# Mainboard.net
KiCad netlist of a schematic drawn in EAGLE
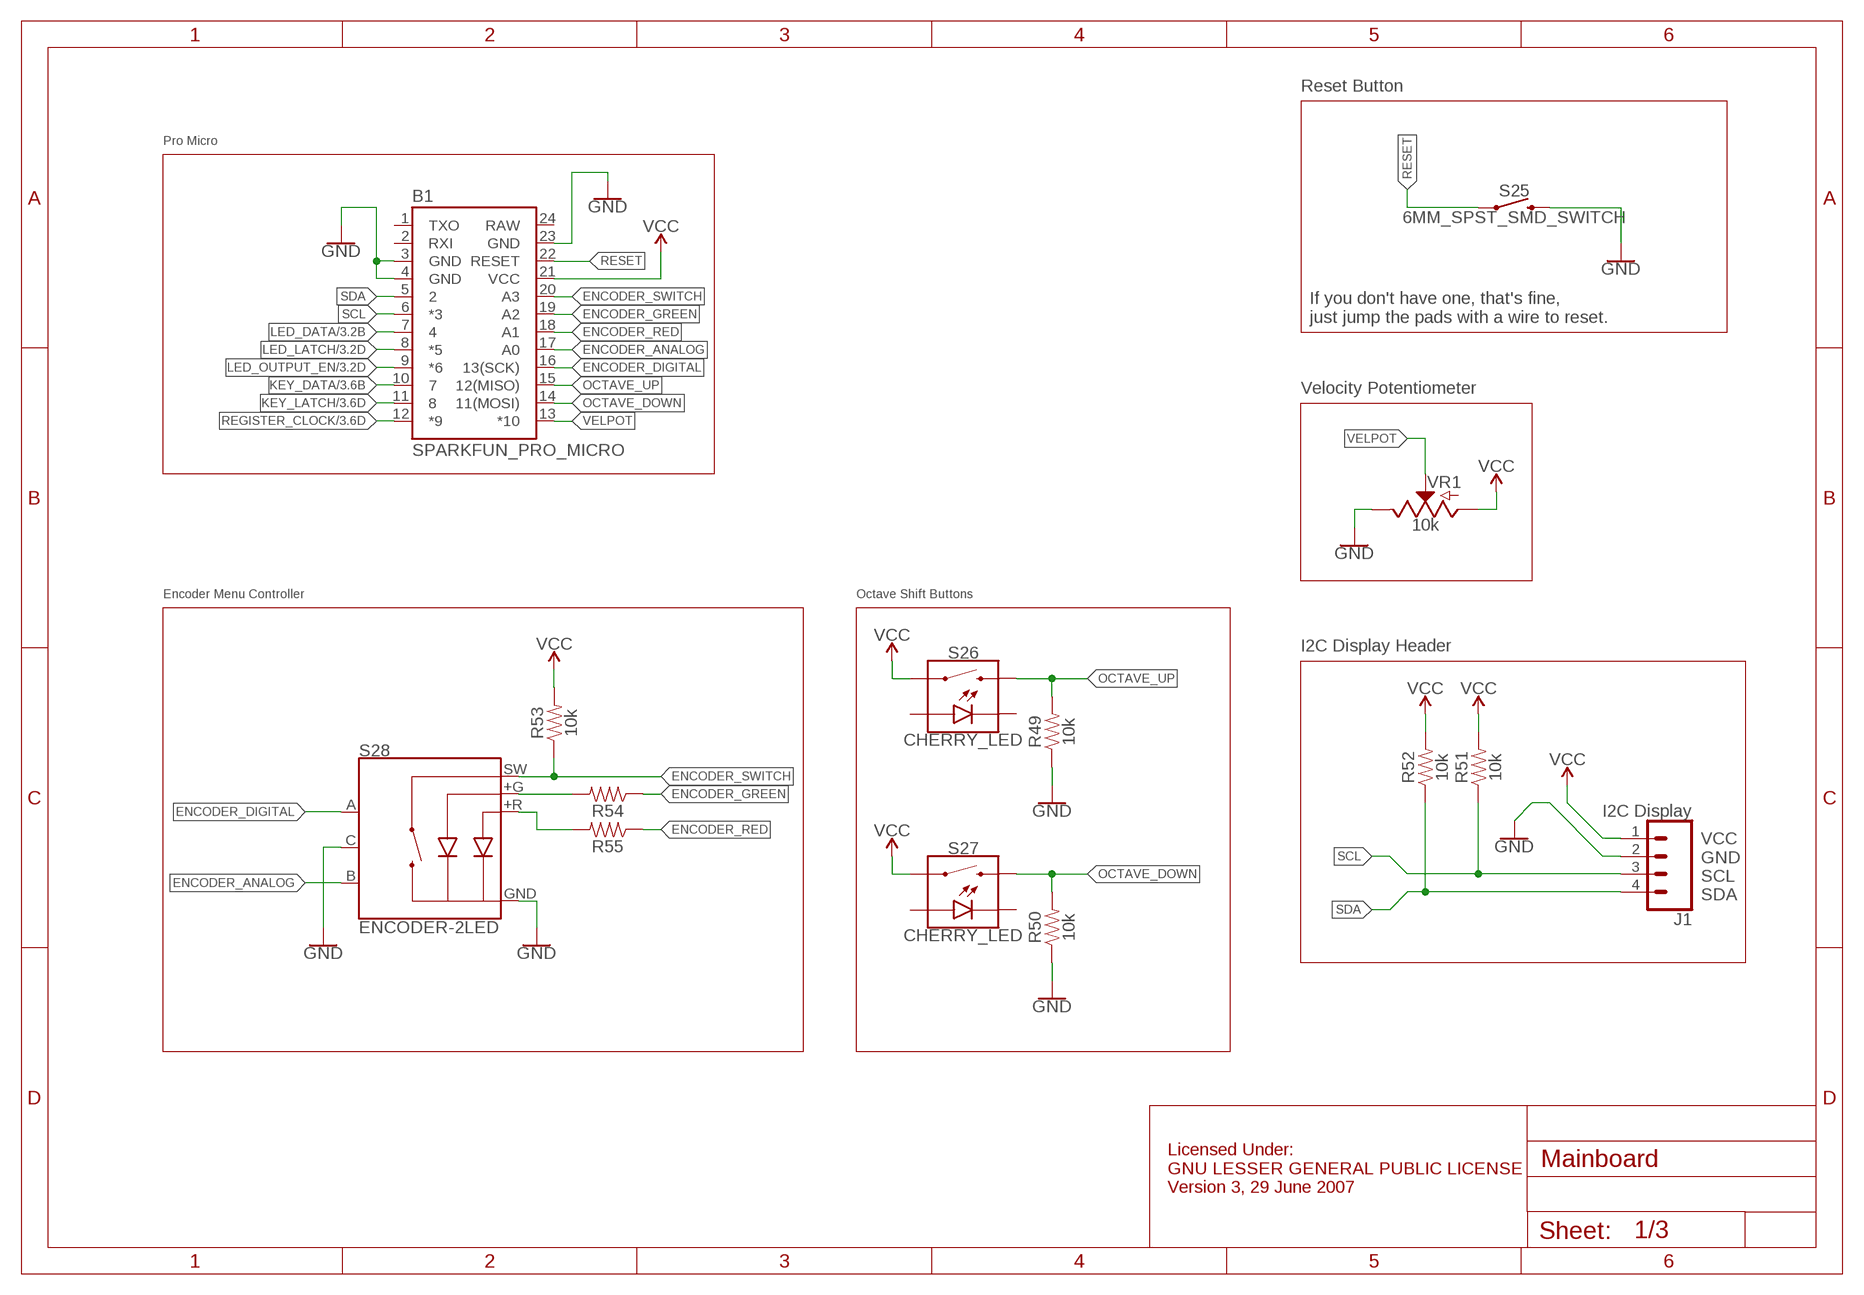
[diagram p0: schematic, sheet 1]
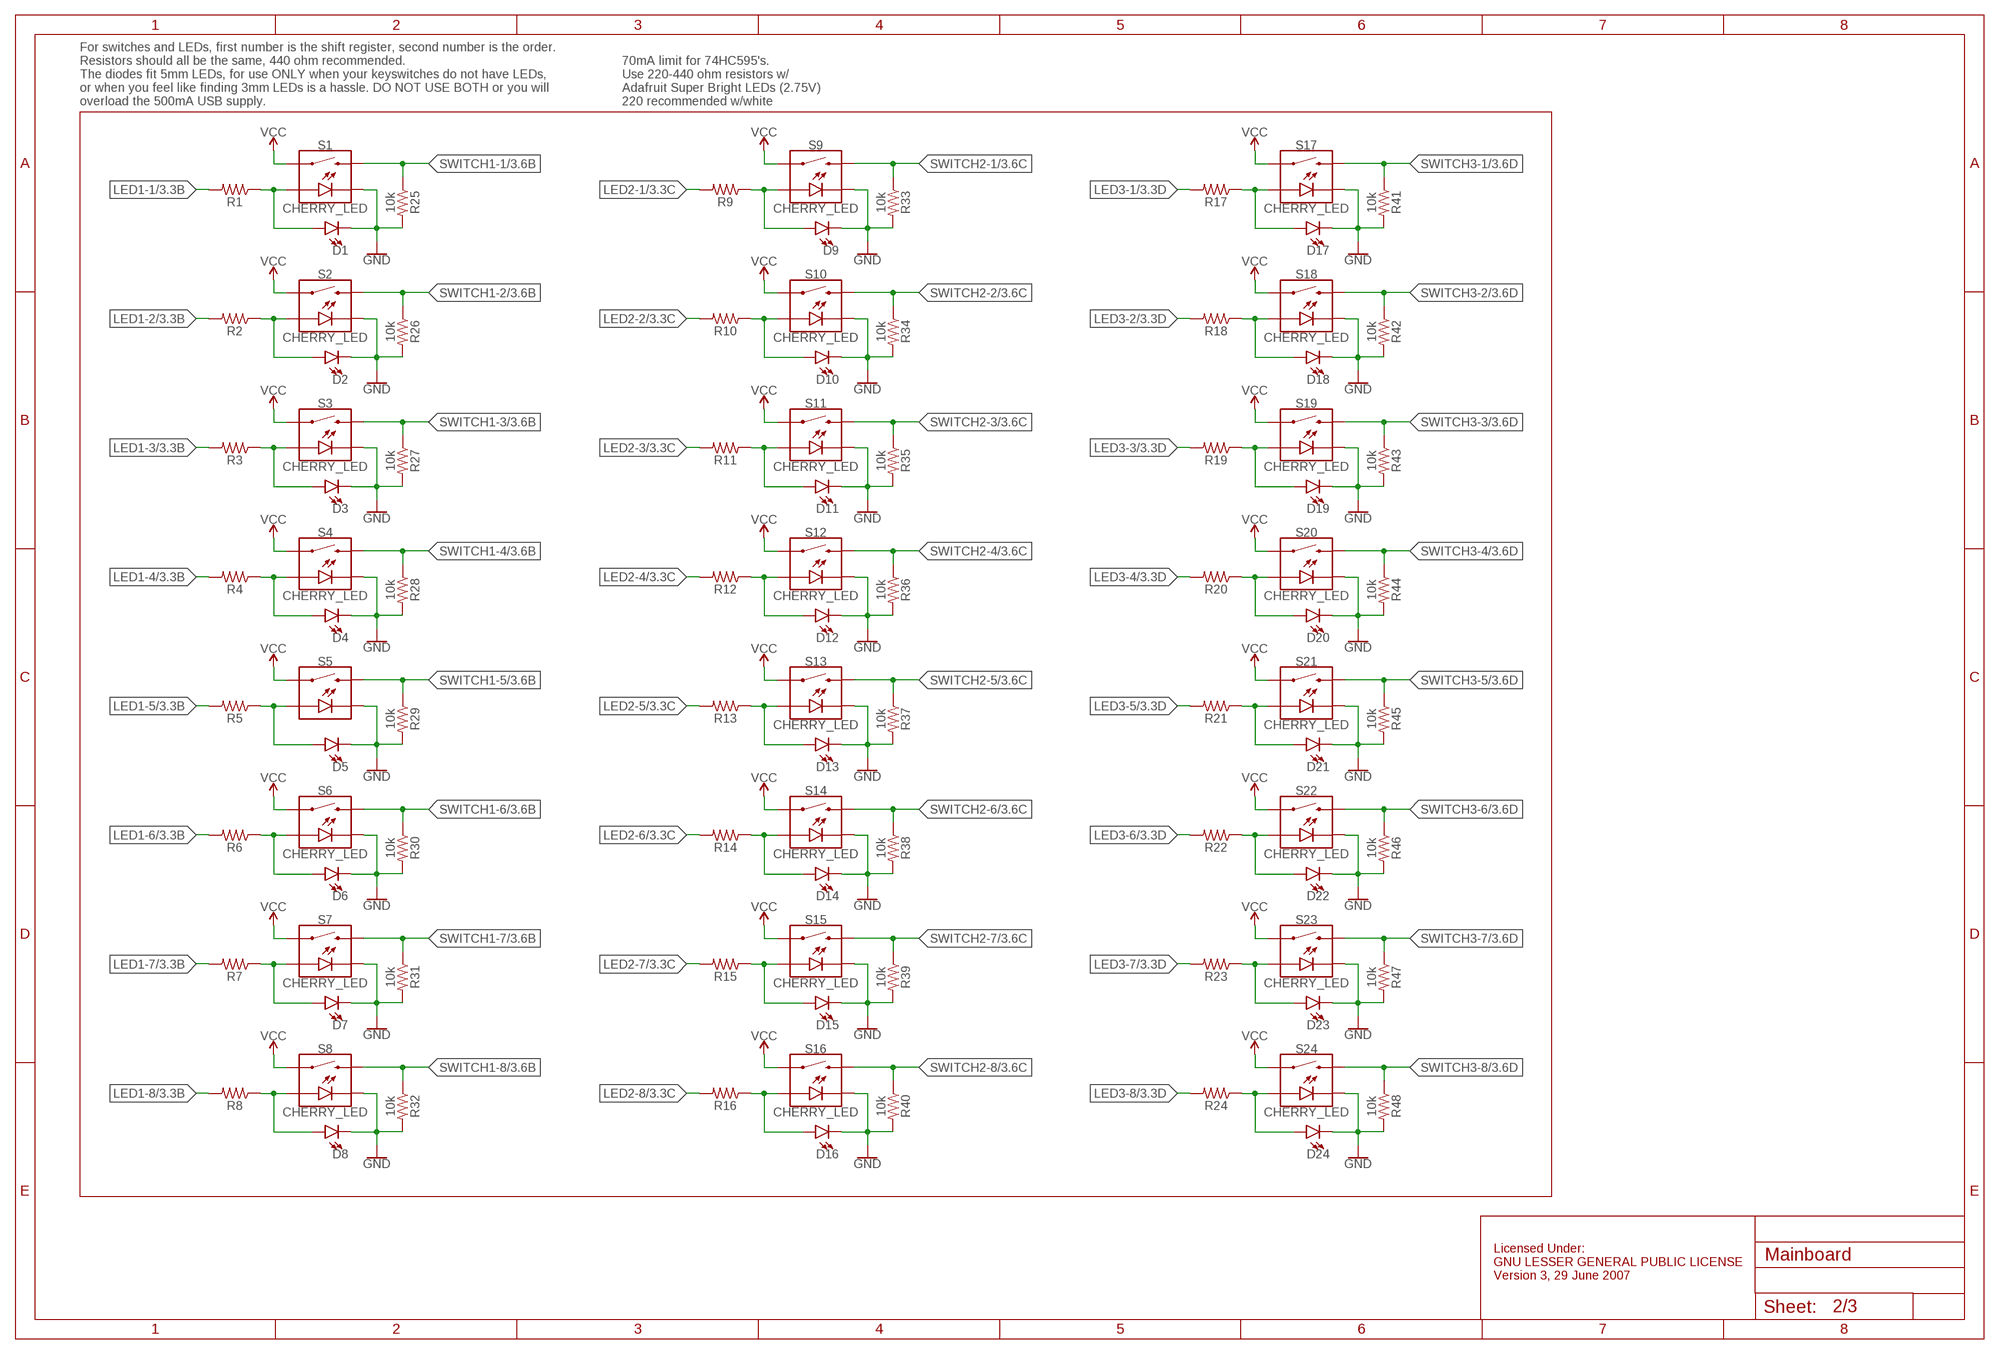
[diagram p1: schematic, sheet 2]
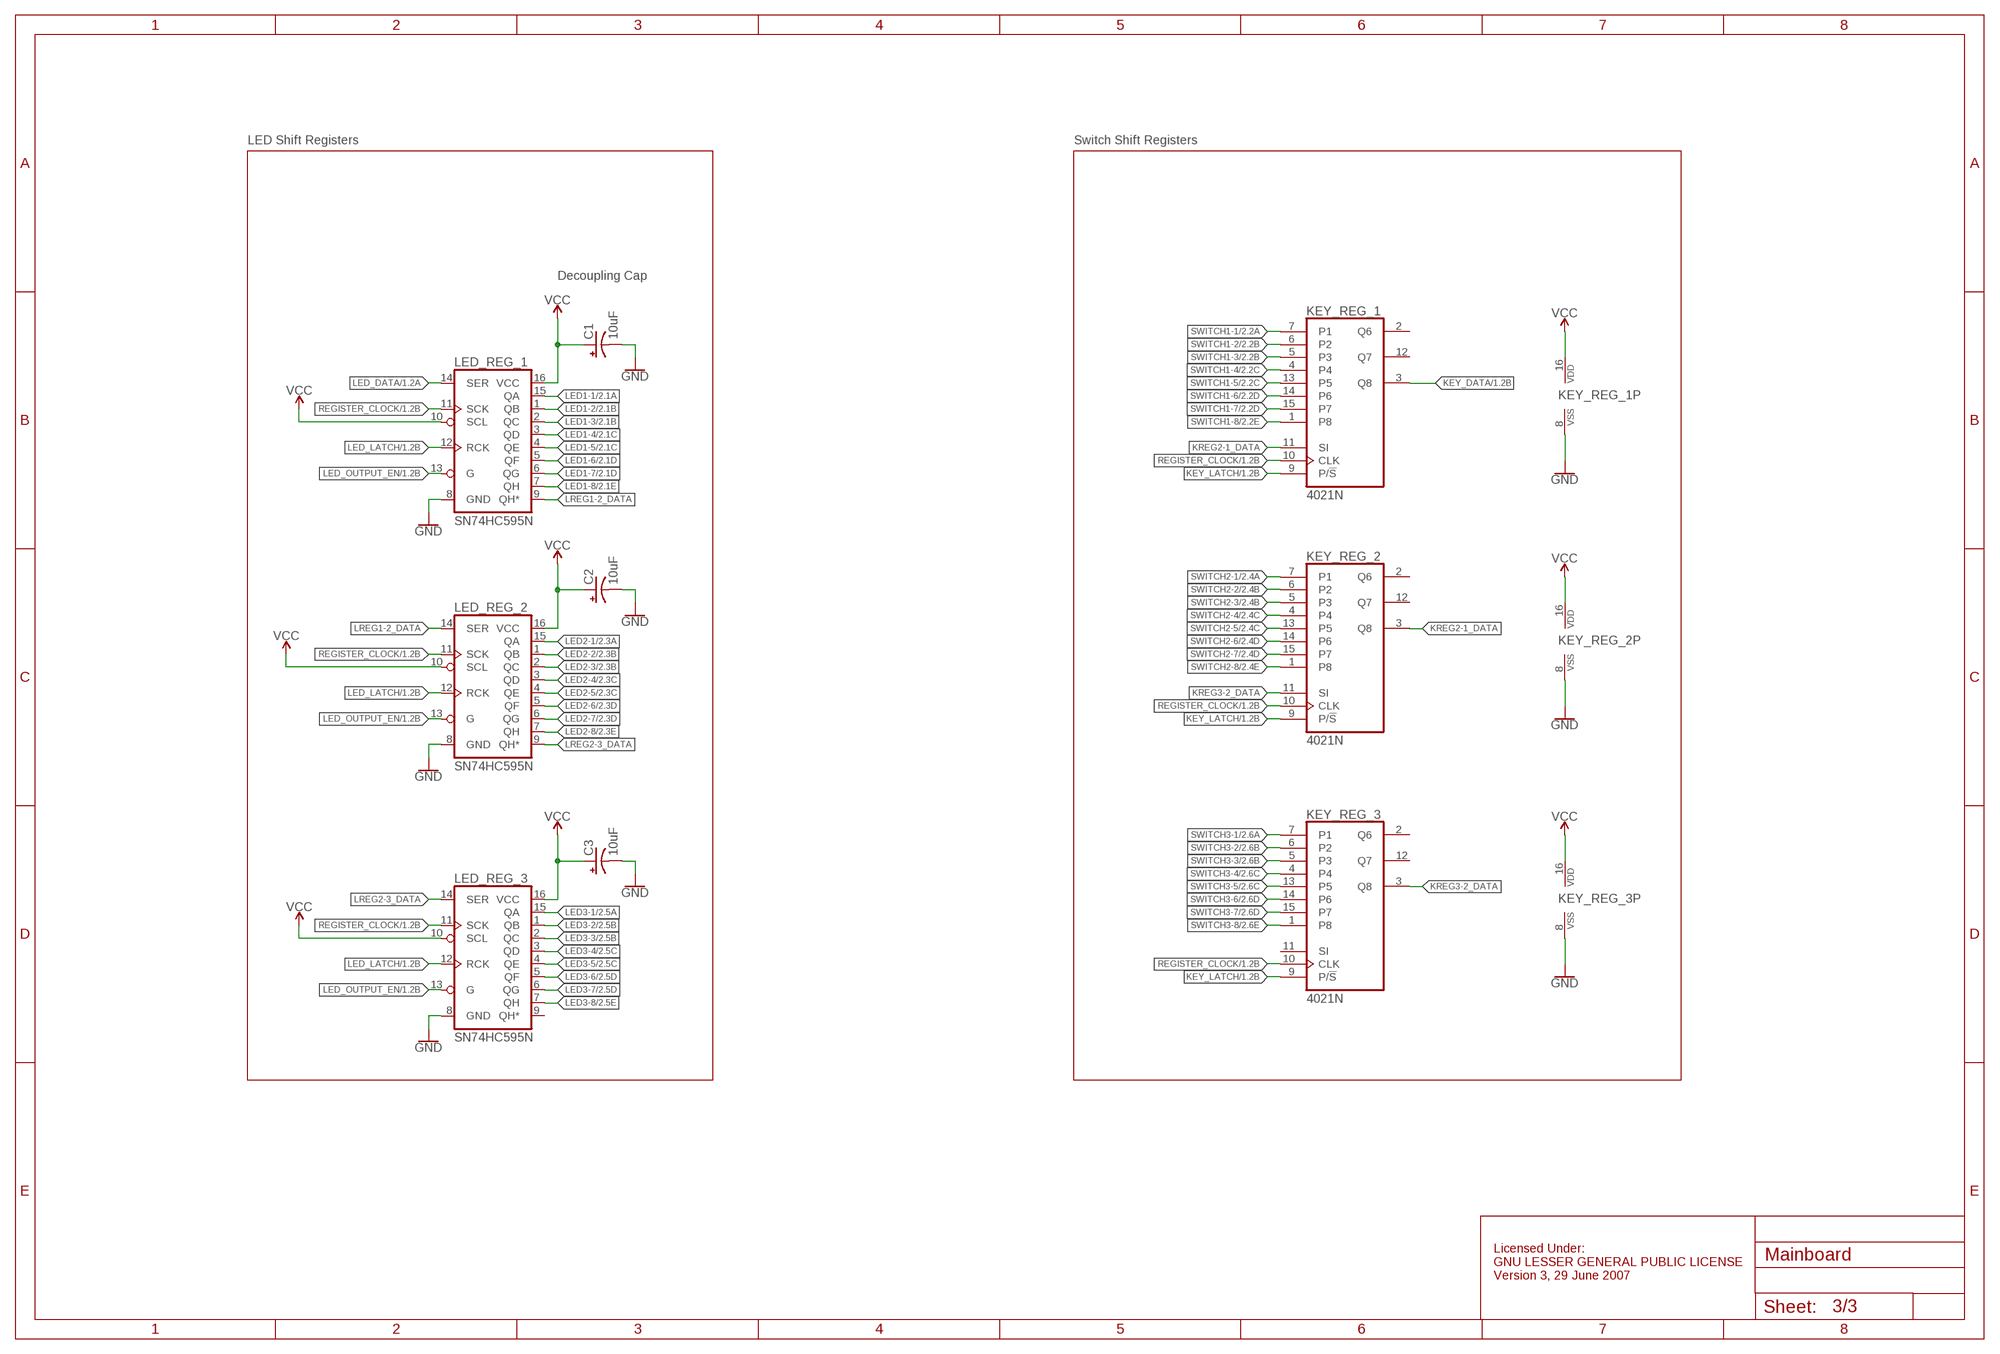
[diagram p2: schematic, sheet 3]

(export (version "E")
  (design (tool "Eeschema 10.0.6"))
  (components
    (comp (ref "D1")
      (value "LED5MM")
      (footprint "eagle-import:LED_5MM")
      (libsource (lib "eagle-import") (part "LED5MM"))
    )
    (comp (ref "D2")
      (value "LED5MM")
      (footprint "eagle-import:LED_5MM")
      (libsource (lib "eagle-import") (part "LED5MM"))
    )
    (comp (ref "D3")
      (value "LED5MM")
      (footprint "eagle-import:LED_5MM")
      (libsource (lib "eagle-import") (part "LED5MM"))
    )
    (comp (ref "D4")
      (value "LED5MM")
      (footprint "eagle-import:LED_5MM")
      (libsource (lib "eagle-import") (part "LED5MM"))
    )
    (comp (ref "D5")
      (value "LED5MM")
      (footprint "eagle-import:LED_5MM")
      (libsource (lib "eagle-import") (part "LED5MM"))
    )
    (comp (ref "D6")
      (value "LED5MM")
      (footprint "eagle-import:LED_5MM")
      (libsource (lib "eagle-import") (part "LED5MM"))
    )
    (comp (ref "D7")
      (value "LED5MM")
      (footprint "eagle-import:LED_5MM")
      (libsource (lib "eagle-import") (part "LED5MM"))
    )
    (comp (ref "D8")
      (value "LED5MM")
      (footprint "eagle-import:LED_5MM")
      (libsource (lib "eagle-import") (part "LED5MM"))
    )
    (comp (ref "D9")
      (value "LED5MM")
      (footprint "eagle-import:LED_5MM")
      (libsource (lib "eagle-import") (part "LED5MM"))
    )
    (comp (ref "D10")
      (value "LED5MM")
      (footprint "eagle-import:LED_5MM")
      (libsource (lib "eagle-import") (part "LED5MM"))
    )
    (comp (ref "D11")
      (value "LED5MM")
      (footprint "eagle-import:LED_5MM")
      (libsource (lib "eagle-import") (part "LED5MM"))
    )
    (comp (ref "D12")
      (value "LED5MM")
      (footprint "eagle-import:LED_5MM")
      (libsource (lib "eagle-import") (part "LED5MM"))
    )
    (comp (ref "D13")
      (value "LED5MM")
      (footprint "eagle-import:LED_5MM")
      (libsource (lib "eagle-import") (part "LED5MM"))
    )
    (comp (ref "D14")
      (value "LED5MM")
      (footprint "eagle-import:LED_5MM")
      (libsource (lib "eagle-import") (part "LED5MM"))
    )
    (comp (ref "D15")
      (value "LED5MM")
      (footprint "eagle-import:LED_5MM")
      (libsource (lib "eagle-import") (part "LED5MM"))
    )
    (comp (ref "D16")
      (value "LED5MM")
      (footprint "eagle-import:LED_5MM")
      (libsource (lib "eagle-import") (part "LED5MM"))
    )
    (comp (ref "D17")
      (value "LED5MM")
      (footprint "eagle-import:LED_5MM")
      (libsource (lib "eagle-import") (part "LED5MM"))
    )
    (comp (ref "D18")
      (value "LED5MM")
      (footprint "eagle-import:LED_5MM")
      (libsource (lib "eagle-import") (part "LED5MM"))
    )
    (comp (ref "D19")
      (value "LED5MM")
      (footprint "eagle-import:LED_5MM")
      (libsource (lib "eagle-import") (part "LED5MM"))
    )
    (comp (ref "D20")
      (value "LED5MM")
      (footprint "eagle-import:LED_5MM")
      (libsource (lib "eagle-import") (part "LED5MM"))
    )
    (comp (ref "D21")
      (value "LED5MM")
      (footprint "eagle-import:LED_5MM")
      (libsource (lib "eagle-import") (part "LED5MM"))
    )
    (comp (ref "D22")
      (value "LED5MM")
      (footprint "eagle-import:LED_5MM")
      (libsource (lib "eagle-import") (part "LED5MM"))
    )
    (comp (ref "D23")
      (value "LED5MM")
      (footprint "eagle-import:LED_5MM")
      (libsource (lib "eagle-import") (part "LED5MM"))
    )
    (comp (ref "D24")
      (value "LED5MM")
      (footprint "eagle-import:LED_5MM")
      (libsource (lib "eagle-import") (part "LED5MM"))
    )
    (comp (ref "R1")
      (value "RESISTORAXIAL-0.3")
      (footprint "eagle-import:AXIAL-0.3")
      (libsource (lib "eagle-import") (part "RESISTORAXIAL-0.3"))
    )
    (comp (ref "R2")
      (value "RESISTORAXIAL-0.3")
      (footprint "eagle-import:AXIAL-0.3")
      (libsource (lib "eagle-import") (part "RESISTORAXIAL-0.3"))
    )
    (comp (ref "R3")
      (value "RESISTORAXIAL-0.3")
      (footprint "eagle-import:AXIAL-0.3")
      (libsource (lib "eagle-import") (part "RESISTORAXIAL-0.3"))
    )
    (comp (ref "R4")
      (value "RESISTORAXIAL-0.3")
      (footprint "eagle-import:AXIAL-0.3")
      (libsource (lib "eagle-import") (part "RESISTORAXIAL-0.3"))
    )
    (comp (ref "R5")
      (value "RESISTORAXIAL-0.3")
      (footprint "eagle-import:AXIAL-0.3")
      (libsource (lib "eagle-import") (part "RESISTORAXIAL-0.3"))
    )
    (comp (ref "R6")
      (value "RESISTORAXIAL-0.3")
      (footprint "eagle-import:AXIAL-0.3")
      (libsource (lib "eagle-import") (part "RESISTORAXIAL-0.3"))
    )
    (comp (ref "R7")
      (value "RESISTORAXIAL-0.3")
      (footprint "eagle-import:AXIAL-0.3")
      (libsource (lib "eagle-import") (part "RESISTORAXIAL-0.3"))
    )
    (comp (ref "R8")
      (value "RESISTORAXIAL-0.3")
      (footprint "eagle-import:AXIAL-0.3")
      (libsource (lib "eagle-import") (part "RESISTORAXIAL-0.3"))
    )
    (comp (ref "R9")
      (value "RESISTORAXIAL-0.3")
      (footprint "eagle-import:AXIAL-0.3")
      (libsource (lib "eagle-import") (part "RESISTORAXIAL-0.3"))
    )
    (comp (ref "R10")
      (value "RESISTORAXIAL-0.3")
      (footprint "eagle-import:AXIAL-0.3")
      (libsource (lib "eagle-import") (part "RESISTORAXIAL-0.3"))
    )
    (comp (ref "R11")
      (value "RESISTORAXIAL-0.3")
      (footprint "eagle-import:AXIAL-0.3")
      (libsource (lib "eagle-import") (part "RESISTORAXIAL-0.3"))
    )
    (comp (ref "R12")
      (value "RESISTORAXIAL-0.3")
      (footprint "eagle-import:AXIAL-0.3")
      (libsource (lib "eagle-import") (part "RESISTORAXIAL-0.3"))
    )
    (comp (ref "R13")
      (value "RESISTORAXIAL-0.3")
      (footprint "eagle-import:AXIAL-0.3")
      (libsource (lib "eagle-import") (part "RESISTORAXIAL-0.3"))
    )
    (comp (ref "R14")
      (value "RESISTORAXIAL-0.3")
      (footprint "eagle-import:AXIAL-0.3")
      (libsource (lib "eagle-import") (part "RESISTORAXIAL-0.3"))
    )
    (comp (ref "R15")
      (value "RESISTORAXIAL-0.3")
      (footprint "eagle-import:AXIAL-0.3")
      (libsource (lib "eagle-import") (part "RESISTORAXIAL-0.3"))
    )
    (comp (ref "R16")
      (value "RESISTORAXIAL-0.3")
      (footprint "eagle-import:AXIAL-0.3")
      (libsource (lib "eagle-import") (part "RESISTORAXIAL-0.3"))
    )
    (comp (ref "R17")
      (value "RESISTORAXIAL-0.3")
      (footprint "eagle-import:AXIAL-0.3")
      (libsource (lib "eagle-import") (part "RESISTORAXIAL-0.3"))
    )
    (comp (ref "R18")
      (value "RESISTORAXIAL-0.3")
      (footprint "eagle-import:AXIAL-0.3")
      (libsource (lib "eagle-import") (part "RESISTORAXIAL-0.3"))
    )
    (comp (ref "R19")
      (value "RESISTORAXIAL-0.3")
      (footprint "eagle-import:AXIAL-0.3")
      (libsource (lib "eagle-import") (part "RESISTORAXIAL-0.3"))
    )
    (comp (ref "R20")
      (value "RESISTORAXIAL-0.3")
      (footprint "eagle-import:AXIAL-0.3")
      (libsource (lib "eagle-import") (part "RESISTORAXIAL-0.3"))
    )
    (comp (ref "R21")
      (value "RESISTORAXIAL-0.3")
      (footprint "eagle-import:AXIAL-0.3")
      (libsource (lib "eagle-import") (part "RESISTORAXIAL-0.3"))
    )
    (comp (ref "R22")
      (value "RESISTORAXIAL-0.3")
      (footprint "eagle-import:AXIAL-0.3")
      (libsource (lib "eagle-import") (part "RESISTORAXIAL-0.3"))
    )
    (comp (ref "R23")
      (value "RESISTORAXIAL-0.3")
      (footprint "eagle-import:AXIAL-0.3")
      (libsource (lib "eagle-import") (part "RESISTORAXIAL-0.3"))
    )
    (comp (ref "R24")
      (value "RESISTORAXIAL-0.3")
      (footprint "eagle-import:AXIAL-0.3")
      (libsource (lib "eagle-import") (part "RESISTORAXIAL-0.3"))
    )
    (comp (ref "R25")
      (value "10k")
      (footprint "eagle-import:AXIAL-0.3")
      (libsource (lib "eagle-import") (part "10KOHM-HORIZ-1/4W-1%"))
    )
    (comp (ref "R26")
      (value "10k")
      (footprint "eagle-import:AXIAL-0.3")
      (libsource (lib "eagle-import") (part "10KOHM-HORIZ-1/4W-1%"))
    )
    (comp (ref "R27")
      (value "10k")
      (footprint "eagle-import:AXIAL-0.3")
      (libsource (lib "eagle-import") (part "10KOHM-HORIZ-1/4W-1%"))
    )
    (comp (ref "R28")
      (value "10k")
      (footprint "eagle-import:AXIAL-0.3")
      (libsource (lib "eagle-import") (part "10KOHM-HORIZ-1/4W-1%"))
    )
    (comp (ref "R29")
      (value "10k")
      (footprint "eagle-import:AXIAL-0.3")
      (libsource (lib "eagle-import") (part "10KOHM-HORIZ-1/4W-1%"))
    )
    (comp (ref "R30")
      (value "10k")
      (footprint "eagle-import:AXIAL-0.3")
      (libsource (lib "eagle-import") (part "10KOHM-HORIZ-1/4W-1%"))
    )
    (comp (ref "R31")
      (value "10k")
      (footprint "eagle-import:AXIAL-0.3")
      (libsource (lib "eagle-import") (part "10KOHM-HORIZ-1/4W-1%"))
    )
    (comp (ref "R32")
      (value "10k")
      (footprint "eagle-import:AXIAL-0.3")
      (libsource (lib "eagle-import") (part "10KOHM-HORIZ-1/4W-1%"))
    )
    (comp (ref "R33")
      (value "10k")
      (footprint "eagle-import:AXIAL-0.3")
      (libsource (lib "eagle-import") (part "10KOHM-HORIZ-1/4W-1%"))
    )
    (comp (ref "R34")
      (value "10k")
      (footprint "eagle-import:AXIAL-0.3")
      (libsource (lib "eagle-import") (part "10KOHM-HORIZ-1/4W-1%"))
    )
    (comp (ref "R35")
      (value "10k")
      (footprint "eagle-import:AXIAL-0.3")
      (libsource (lib "eagle-import") (part "10KOHM-HORIZ-1/4W-1%"))
    )
    (comp (ref "R36")
      (value "10k")
      (footprint "eagle-import:AXIAL-0.3")
      (libsource (lib "eagle-import") (part "10KOHM-HORIZ-1/4W-1%"))
    )
    (comp (ref "R37")
      (value "10k")
      (footprint "eagle-import:AXIAL-0.3")
      (libsource (lib "eagle-import") (part "10KOHM-HORIZ-1/4W-1%"))
    )
    (comp (ref "R38")
      (value "10k")
      (footprint "eagle-import:AXIAL-0.3")
      (libsource (lib "eagle-import") (part "10KOHM-HORIZ-1/4W-1%"))
    )
    (comp (ref "R39")
      (value "10k")
      (footprint "eagle-import:AXIAL-0.3")
      (libsource (lib "eagle-import") (part "10KOHM-HORIZ-1/4W-1%"))
    )
    (comp (ref "R40")
      (value "10k")
      (footprint "eagle-import:AXIAL-0.3")
      (libsource (lib "eagle-import") (part "10KOHM-HORIZ-1/4W-1%"))
    )
    (comp (ref "R41")
      (value "10k")
      (footprint "eagle-import:AXIAL-0.3")
      (libsource (lib "eagle-import") (part "10KOHM-HORIZ-1/4W-1%"))
    )
    (comp (ref "R42")
      (value "10k")
      (footprint "eagle-import:AXIAL-0.3")
      (libsource (lib "eagle-import") (part "10KOHM-HORIZ-1/4W-1%"))
    )
    (comp (ref "R43")
      (value "10k")
      (footprint "eagle-import:AXIAL-0.3")
      (libsource (lib "eagle-import") (part "10KOHM-HORIZ-1/4W-1%"))
    )
    (comp (ref "R44")
      (value "10k")
      (footprint "eagle-import:AXIAL-0.3")
      (libsource (lib "eagle-import") (part "10KOHM-HORIZ-1/4W-1%"))
    )
    (comp (ref "R45")
      (value "10k")
      (footprint "eagle-import:AXIAL-0.3")
      (libsource (lib "eagle-import") (part "10KOHM-HORIZ-1/4W-1%"))
    )
    (comp (ref "R46")
      (value "10k")
      (footprint "eagle-import:AXIAL-0.3")
      (libsource (lib "eagle-import") (part "10KOHM-HORIZ-1/4W-1%"))
    )
    (comp (ref "R47")
      (value "10k")
      (footprint "eagle-import:AXIAL-0.3")
      (libsource (lib "eagle-import") (part "10KOHM-HORIZ-1/4W-1%"))
    )
    (comp (ref "R48")
      (value "10k")
      (footprint "eagle-import:AXIAL-0.3")
      (libsource (lib "eagle-import") (part "10KOHM-HORIZ-1/4W-1%"))
    )
    (comp (ref "S1")
      (value "CHERRY_LED")
      (footprint "eagle-import:CHERRY-MX-LED")
      (libsource (lib "eagle-import") (part "MOMENTARY-SWITCH-SPST-LED-PTH-CHERRY"))
    )
    (comp (ref "S2")
      (value "CHERRY_LED")
      (footprint "eagle-import:CHERRY-MX-LED")
      (libsource (lib "eagle-import") (part "MOMENTARY-SWITCH-SPST-LED-PTH-CHERRY"))
    )
    (comp (ref "S3")
      (value "CHERRY_LED")
      (footprint "eagle-import:CHERRY-MX-LED")
      (libsource (lib "eagle-import") (part "MOMENTARY-SWITCH-SPST-LED-PTH-CHERRY"))
    )
    (comp (ref "S4")
      (value "CHERRY_LED")
      (footprint "eagle-import:CHERRY-MX-LED")
      (libsource (lib "eagle-import") (part "MOMENTARY-SWITCH-SPST-LED-PTH-CHERRY"))
    )
    (comp (ref "S5")
      (value "MOMENTARY-SWITCH-SPST-LED-PTH-CHERRY")
      (footprint "eagle-import:CHERRY-MX-LED")
      (libsource (lib "eagle-import") (part "MOMENTARY-SWITCH-SPST-LED-PTH-CHERRY"))
    )
    (comp (ref "S6")
      (value "CHERRY_LED")
      (footprint "eagle-import:CHERRY-MX-LED")
      (libsource (lib "eagle-import") (part "MOMENTARY-SWITCH-SPST-LED-PTH-CHERRY"))
    )
    (comp (ref "S7")
      (value "CHERRY_LED")
      (footprint "eagle-import:CHERRY-MX-LED")
      (libsource (lib "eagle-import") (part "MOMENTARY-SWITCH-SPST-LED-PTH-CHERRY"))
    )
    (comp (ref "S8")
      (value "CHERRY_LED")
      (footprint "eagle-import:CHERRY-MX-LED")
      (libsource (lib "eagle-import") (part "MOMENTARY-SWITCH-SPST-LED-PTH-CHERRY"))
    )
    (comp (ref "S9")
      (value "CHERRY_LED")
      (footprint "eagle-import:CHERRY-MX-LED")
      (libsource (lib "eagle-import") (part "MOMENTARY-SWITCH-SPST-LED-PTH-CHERRY"))
    )
    (comp (ref "S10")
      (value "CHERRY_LED")
      (footprint "eagle-import:CHERRY-MX-LED")
      (libsource (lib "eagle-import") (part "MOMENTARY-SWITCH-SPST-LED-PTH-CHERRY"))
    )
    (comp (ref "S11")
      (value "CHERRY_LED")
      (footprint "eagle-import:CHERRY-MX-LED")
      (libsource (lib "eagle-import") (part "MOMENTARY-SWITCH-SPST-LED-PTH-CHERRY"))
    )
    (comp (ref "S12")
      (value "CHERRY_LED")
      (footprint "eagle-import:CHERRY-MX-LED")
      (libsource (lib "eagle-import") (part "MOMENTARY-SWITCH-SPST-LED-PTH-CHERRY"))
    )
    (comp (ref "S13")
      (value "CHERRY_LED")
      (footprint "eagle-import:CHERRY-MX-LED")
      (libsource (lib "eagle-import") (part "MOMENTARY-SWITCH-SPST-LED-PTH-CHERRY"))
    )
    (comp (ref "S14")
      (value "CHERRY_LED")
      (footprint "eagle-import:CHERRY-MX-LED")
      (libsource (lib "eagle-import") (part "MOMENTARY-SWITCH-SPST-LED-PTH-CHERRY"))
    )
    (comp (ref "S15")
      (value "CHERRY_LED")
      (footprint "eagle-import:CHERRY-MX-LED")
      (libsource (lib "eagle-import") (part "MOMENTARY-SWITCH-SPST-LED-PTH-CHERRY"))
    )
    (comp (ref "S16")
      (value "CHERRY_LED")
      (footprint "eagle-import:CHERRY-MX-LED")
      (libsource (lib "eagle-import") (part "MOMENTARY-SWITCH-SPST-LED-PTH-CHERRY"))
    )
    (comp (ref "S17")
      (value "CHERRY_LED")
      (footprint "eagle-import:CHERRY-MX-LED")
      (libsource (lib "eagle-import") (part "MOMENTARY-SWITCH-SPST-LED-PTH-CHERRY"))
    )
    (comp (ref "S18")
      (value "CHERRY_LED")
      (footprint "eagle-import:CHERRY-MX-LED")
      (libsource (lib "eagle-import") (part "MOMENTARY-SWITCH-SPST-LED-PTH-CHERRY"))
    )
    (comp (ref "S19")
      (value "CHERRY_LED")
      (footprint "eagle-import:CHERRY-MX-LED")
      (libsource (lib "eagle-import") (part "MOMENTARY-SWITCH-SPST-LED-PTH-CHERRY"))
    )
    (comp (ref "S20")
      (value "CHERRY_LED")
      (footprint "eagle-import:CHERRY-MX-LED")
      (libsource (lib "eagle-import") (part "MOMENTARY-SWITCH-SPST-LED-PTH-CHERRY"))
    )
    (comp (ref "S21")
      (value "CHERRY_LED")
      (footprint "eagle-import:CHERRY-MX-LED")
      (libsource (lib "eagle-import") (part "MOMENTARY-SWITCH-SPST-LED-PTH-CHERRY"))
    )
    (comp (ref "S22")
      (value "CHERRY_LED")
      (footprint "eagle-import:CHERRY-MX-LED")
      (libsource (lib "eagle-import") (part "MOMENTARY-SWITCH-SPST-LED-PTH-CHERRY"))
    )
    (comp (ref "S23")
      (value "CHERRY_LED")
      (footprint "eagle-import:CHERRY-MX-LED")
      (libsource (lib "eagle-import") (part "MOMENTARY-SWITCH-SPST-LED-PTH-CHERRY"))
    )
    (comp (ref "S24")
      (value "CHERRY_LED")
      (footprint "eagle-import:CHERRY-MX-LED")
      (libsource (lib "eagle-import") (part "MOMENTARY-SWITCH-SPST-LED-PTH-CHERRY"))
    )
    (comp (ref "B1")
      (value "SPARKFUN_PRO_MICRO")
      (footprint "eagle-import:SPARKFUN_PRO_MICRO")
      (libsource (lib "eagle-import") (part "SPARKFUN_PRO_MICRO"))
    )
    (comp (ref "J1")
      (value "I2C Display")
      (footprint "eagle-import:1X04")
      (libsource (lib "eagle-import") (part "CONN_04"))
    )
    (comp (ref "R49")
      (value "10k")
      (footprint "eagle-import:AXIAL-0.3")
      (libsource (lib "eagle-import") (part "10KOHM-HORIZ-1/4W-1%"))
    )
    (comp (ref "R50")
      (value "10k")
      (footprint "eagle-import:AXIAL-0.3")
      (libsource (lib "eagle-import") (part "10KOHM-HORIZ-1/4W-1%"))
    )
    (comp (ref "R51")
      (value "10k")
      (footprint "eagle-import:AXIAL-0.3")
      (libsource (lib "eagle-import") (part "10KOHM-HORIZ-1/4W-1%"))
    )
    (comp (ref "R52")
      (value "10k")
      (footprint "eagle-import:AXIAL-0.3")
      (libsource (lib "eagle-import") (part "10KOHM-HORIZ-1/4W-1%"))
    )
    (comp (ref "R53")
      (value "10k")
      (footprint "eagle-import:AXIAL-0.3")
      (libsource (lib "eagle-import") (part "10KOHM-HORIZ-1/4W-1%"))
    )
    (comp (ref "R54")
      (value "RESISTORAXIAL-0.3")
      (footprint "eagle-import:AXIAL-0.3")
      (libsource (lib "eagle-import") (part "RESISTORAXIAL-0.3"))
    )
    (comp (ref "R55")
      (value "RESISTORAXIAL-0.3")
      (footprint "eagle-import:AXIAL-0.3")
      (libsource (lib "eagle-import") (part "RESISTORAXIAL-0.3"))
    )
    (comp (ref "S25")
      (value "6MM_SPST_SMD_SWITCH")
      (footprint "eagle-import:TACTILE_SWITCH_SMD_6.0X3.5MM")
      (libsource (lib "eagle-import") (part "MOMENTARY-SWITCH-SPST-SMD-6.0X3.5MM"))
    )
    (comp (ref "S26")
      (value "CHERRY_LED")
      (footprint "eagle-import:CHERRY-MX-LED")
      (libsource (lib "eagle-import") (part "MOMENTARY-SWITCH-SPST-LED-PTH-CHERRY"))
    )
    (comp (ref "S27")
      (value "CHERRY_LED")
      (footprint "eagle-import:CHERRY-MX-LED")
      (libsource (lib "eagle-import") (part "MOMENTARY-SWITCH-SPST-LED-PTH-CHERRY"))
    )
    (comp (ref "S28")
      (value "ENCODER-2LED")
      (footprint "eagle-import:ENCODER_LED_2")
      (libsource (lib "eagle-import") (part "ENCODER-2LED"))
    )
    (comp (ref "VR1")
      (value "10k")
      (footprint "eagle-import:POT-PTH-ALPS")
      (libsource (lib "eagle-import") (part "POTENTIOMETER-PTH-9MM-1/20W-20%"))
    )
    (comp (ref "C1")
      (value "10uF")
      (footprint "eagle-import:CPOL-RADIAL-2.5MM-5MM")
      (libsource (lib "eagle-import") (part "10UF-POLAR-RADIAL-2.5MM-25V-20%"))
    )
    (comp (ref "C2")
      (value "10uF")
      (footprint "eagle-import:CPOL-RADIAL-2.5MM-5MM")
      (libsource (lib "eagle-import") (part "10UF-POLAR-RADIAL-2.5MM-25V-20%"))
    )
    (comp (ref "C3")
      (value "10uF")
      (footprint "eagle-import:CPOL-RADIAL-2.5MM-5MM")
      (libsource (lib "eagle-import") (part "10UF-POLAR-RADIAL-2.5MM-25V-20%"))
    )
    (comp (ref "KEY_REG_1")
      (value "4021N")
      (footprint "eagle-import:DIL16")
      (libsource (lib "eagle-import") (part "4021N"))
    )
    (comp (ref "KEY_REG_2")
      (value "4021N")
      (footprint "eagle-import:DIL16")
      (libsource (lib "eagle-import") (part "4021N"))
    )
    (comp (ref "KEY_REG_3")
      (value "4021N")
      (footprint "eagle-import:DIL16")
      (libsource (lib "eagle-import") (part "4021N"))
    )
    (comp (ref "LED_REG_1")
      (value "SN74HC595N")
      (footprint "eagle-import:DIP16")
      (libsource (lib "eagle-import") (part "74595NHC"))
    )
    (comp (ref "LED_REG_2")
      (value "SN74HC595N")
      (footprint "eagle-import:DIP16")
      (libsource (lib "eagle-import") (part "74595NHC"))
    )
    (comp (ref "LED_REG_3")
      (value "SN74HC595N")
      (footprint "eagle-import:DIP16")
      (libsource (lib "eagle-import") (part "74595NHC"))
    )
  )
  (nets
    (net (code "1") (name "ENCODER_ANALOG") (class "Default")
      (node (ref "B1") (pin "17") (pinfunction "A0_17") (pintype "bidirectional"))
      (node (ref "S28") (pin "B") (pinfunction "B_B") (pintype "bidirectional"))
    )
    (net (code "2") (name "ENCODER_DIGITAL") (class "Default")
      (node (ref "B1") (pin "16") (pinfunction "13(SCK)_16") (pintype "bidirectional"))
      (node (ref "S28") (pin "A") (pinfunction "A_A") (pintype "bidirectional"))
    )
    (net (code "3") (name "ENCODER_GREEN") (class "Default")
      (node (ref "B1") (pin "19") (pinfunction "A2_19") (pintype "bidirectional"))
      (node (ref "R54") (pin "P$1") (pinfunction "1_P$1") (pintype "passive"))
    )
    (net (code "4") (name "ENCODER_RED") (class "Default")
      (node (ref "B1") (pin "18") (pinfunction "A1_18") (pintype "bidirectional"))
      (node (ref "R55") (pin "P$1") (pinfunction "1_P$1") (pintype "passive"))
    )
    (net (code "5") (name "ENCODER_SWITCH") (class "Default")
      (node (ref "B1") (pin "20") (pinfunction "A3_20") (pintype "bidirectional"))
      (node (ref "R53") (pin "P$1") (pinfunction "1_P$1") (pintype "passive"))
      (node (ref "S28") (pin "SW") (pinfunction "SW_SW") (pintype "passive"))
    )
    (net (code "6") (name "GND") (class "Default")
      (node (ref "B1") (pin "23") (pinfunction "GND_23") (pintype "power_in"))
      (node (ref "B1") (pin "3") (pinfunction "GND_3") (pintype "power_in"))
      (node (ref "B1") (pin "4") (pinfunction "GND_4") (pintype "power_in"))
      (node (ref "C1") (pin "2") (pinfunction "-_2") (pintype "passive"))
      (node (ref "C2") (pin "2") (pinfunction "-_2") (pintype "passive"))
      (node (ref "C3") (pin "2") (pinfunction "-_2") (pintype "passive"))
      (node (ref "D1") (pin "K") (pinfunction "C_K") (pintype "passive"))
      (node (ref "D10") (pin "K") (pinfunction "C_K") (pintype "passive"))
      (node (ref "D11") (pin "K") (pinfunction "C_K") (pintype "passive"))
      (node (ref "D12") (pin "K") (pinfunction "C_K") (pintype "passive"))
      (node (ref "D13") (pin "K") (pinfunction "C_K") (pintype "passive"))
      (node (ref "D14") (pin "K") (pinfunction "C_K") (pintype "passive"))
      (node (ref "D15") (pin "K") (pinfunction "C_K") (pintype "passive"))
      (node (ref "D16") (pin "K") (pinfunction "C_K") (pintype "passive"))
      (node (ref "D17") (pin "K") (pinfunction "C_K") (pintype "passive"))
      (node (ref "D18") (pin "K") (pinfunction "C_K") (pintype "passive"))
      (node (ref "D19") (pin "K") (pinfunction "C_K") (pintype "passive"))
      (node (ref "D2") (pin "K") (pinfunction "C_K") (pintype "passive"))
      (node (ref "D20") (pin "K") (pinfunction "C_K") (pintype "passive"))
      (node (ref "D21") (pin "K") (pinfunction "C_K") (pintype "passive"))
      (node (ref "D22") (pin "K") (pinfunction "C_K") (pintype "passive"))
      (node (ref "D23") (pin "K") (pinfunction "C_K") (pintype "passive"))
      (node (ref "D24") (pin "K") (pinfunction "C_K") (pintype "passive"))
      (node (ref "D3") (pin "K") (pinfunction "C_K") (pintype "passive"))
      (node (ref "D4") (pin "K") (pinfunction "C_K") (pintype "passive"))
      (node (ref "D5") (pin "K") (pinfunction "C_K") (pintype "passive"))
      (node (ref "D6") (pin "K") (pinfunction "C_K") (pintype "passive"))
      (node (ref "D7") (pin "K") (pinfunction "C_K") (pintype "passive"))
      (node (ref "D8") (pin "K") (pinfunction "C_K") (pintype "passive"))
      (node (ref "D9") (pin "K") (pinfunction "C_K") (pintype "passive"))
      (node (ref "J1") (pin "2") (pinfunction "2_2") (pintype "passive"))
      (node (ref "KEY_REG_1") (pin "8") (pinfunction "VSS_8") (pintype "power_in"))
      (node (ref "KEY_REG_2") (pin "8") (pinfunction "VSS_8") (pintype "power_in"))
      (node (ref "KEY_REG_3") (pin "8") (pinfunction "VSS_8") (pintype "power_in"))
      (node (ref "LED_REG_1") (pin "8") (pinfunction "GND_8") (pintype "power_in"))
      (node (ref "LED_REG_2") (pin "8") (pinfunction "GND_8") (pintype "power_in"))
      (node (ref "LED_REG_3") (pin "8") (pinfunction "GND_8") (pintype "power_in"))
      (node (ref "R25") (pin "P$2") (pinfunction "2_P$2") (pintype "passive"))
      (node (ref "R26") (pin "P$2") (pinfunction "2_P$2") (pintype "passive"))
      (node (ref "R27") (pin "P$2") (pinfunction "2_P$2") (pintype "passive"))
      (node (ref "R28") (pin "P$2") (pinfunction "2_P$2") (pintype "passive"))
      (node (ref "R29") (pin "P$2") (pinfunction "2_P$2") (pintype "passive"))
      (node (ref "R30") (pin "P$2") (pinfunction "2_P$2") (pintype "passive"))
      (node (ref "R31") (pin "P$2") (pinfunction "2_P$2") (pintype "passive"))
      (node (ref "R32") (pin "P$2") (pinfunction "2_P$2") (pintype "passive"))
      (node (ref "R33") (pin "P$2") (pinfunction "2_P$2") (pintype "passive"))
      (node (ref "R34") (pin "P$2") (pinfunction "2_P$2") (pintype "passive"))
      (node (ref "R35") (pin "P$2") (pinfunction "2_P$2") (pintype "passive"))
      (node (ref "R36") (pin "P$2") (pinfunction "2_P$2") (pintype "passive"))
      (node (ref "R37") (pin "P$2") (pinfunction "2_P$2") (pintype "passive"))
      (node (ref "R38") (pin "P$2") (pinfunction "2_P$2") (pintype "passive"))
      (node (ref "R39") (pin "P$2") (pinfunction "2_P$2") (pintype "passive"))
      (node (ref "R40") (pin "P$2") (pinfunction "2_P$2") (pintype "passive"))
      (node (ref "R41") (pin "P$2") (pinfunction "2_P$2") (pintype "passive"))
      (node (ref "R42") (pin "P$2") (pinfunction "2_P$2") (pintype "passive"))
      (node (ref "R43") (pin "P$2") (pinfunction "2_P$2") (pintype "passive"))
      (node (ref "R44") (pin "P$2") (pinfunction "2_P$2") (pintype "passive"))
      (node (ref "R45") (pin "P$2") (pinfunction "2_P$2") (pintype "passive"))
      (node (ref "R46") (pin "P$2") (pinfunction "2_P$2") (pintype "passive"))
      (node (ref "R47") (pin "P$2") (pinfunction "2_P$2") (pintype "passive"))
      (node (ref "R48") (pin "P$2") (pinfunction "2_P$2") (pintype "passive"))
      (node (ref "R49") (pin "P$1") (pinfunction "1_P$1") (pintype "passive"))
      (node (ref "R50") (pin "P$1") (pinfunction "1_P$1") (pintype "passive"))
      (node (ref "S1") (pin "K") (pinfunction "C_K") (pintype "passive"))
      (node (ref "S10") (pin "K") (pinfunction "C_K") (pintype "passive"))
      (node (ref "S11") (pin "K") (pinfunction "C_K") (pintype "passive"))
      (node (ref "S12") (pin "K") (pinfunction "C_K") (pintype "passive"))
      (node (ref "S13") (pin "K") (pinfunction "C_K") (pintype "passive"))
      (node (ref "S14") (pin "K") (pinfunction "C_K") (pintype "passive"))
      (node (ref "S15") (pin "K") (pinfunction "C_K") (pintype "passive"))
      (node (ref "S16") (pin "K") (pinfunction "C_K") (pintype "passive"))
      (node (ref "S17") (pin "K") (pinfunction "C_K") (pintype "passive"))
      (node (ref "S18") (pin "K") (pinfunction "C_K") (pintype "passive"))
      (node (ref "S19") (pin "K") (pinfunction "C_K") (pintype "passive"))
      (node (ref "S2") (pin "K") (pinfunction "C_K") (pintype "passive"))
      (node (ref "S20") (pin "K") (pinfunction "C_K") (pintype "passive"))
      (node (ref "S21") (pin "K") (pinfunction "C_K") (pintype "passive"))
      (node (ref "S22") (pin "K") (pinfunction "C_K") (pintype "passive"))
      (node (ref "S23") (pin "K") (pinfunction "C_K") (pintype "passive"))
      (node (ref "S24") (pin "K") (pinfunction "C_K") (pintype "passive"))
      (node (ref "S25") (pin "2") (pinfunction "2_2") (pintype "passive"))
      (node (ref "S28") (pin "C") (pinfunction "C_C") (pintype "bidirectional"))
      (node (ref "S28") (pin "GND") (pinfunction "-_GND") (pintype "passive"))
      (node (ref "S3") (pin "K") (pinfunction "C_K") (pintype "passive"))
      (node (ref "S4") (pin "K") (pinfunction "C_K") (pintype "passive"))
      (node (ref "S5") (pin "K") (pinfunction "C_K") (pintype "passive"))
      (node (ref "S6") (pin "K") (pinfunction "C_K") (pintype "passive"))
      (node (ref "S7") (pin "K") (pinfunction "C_K") (pintype "passive"))
      (node (ref "S8") (pin "K") (pinfunction "C_K") (pintype "passive"))
      (node (ref "S9") (pin "K") (pinfunction "C_K") (pintype "passive"))
      (node (ref "VR1") (pin "P$1") (pinfunction "E_P$1") (pintype "passive"))
    )
    (net (code "7") (name "KEY_DATA") (class "Default")
      (node (ref "B1") (pin "10") (pinfunction "7_10") (pintype "bidirectional"))
      (node (ref "KEY_REG_1") (pin "3") (pinfunction "Q8_3") (pintype "output"))
    )
    (net (code "8") (name "KEY_LATCH") (class "Default")
      (node (ref "B1") (pin "11") (pinfunction "8_11") (pintype "bidirectional"))
      (node (ref "KEY_REG_1") (pin "9") (pinfunction "P/~{S}_9") (pintype "input"))
      (node (ref "KEY_REG_2") (pin "9") (pinfunction "P/~{S}_9") (pintype "input"))
      (node (ref "KEY_REG_3") (pin "9") (pinfunction "P/~{S}_9") (pintype "input"))
    )
    (net (code "9") (name "KREG2-1_DATA") (class "Default")
      (node (ref "KEY_REG_1") (pin "11") (pinfunction "SI_11") (pintype "input"))
      (node (ref "KEY_REG_2") (pin "3") (pinfunction "Q8_3") (pintype "output"))
    )
    (net (code "10") (name "KREG3-2_DATA") (class "Default")
      (node (ref "KEY_REG_2") (pin "11") (pinfunction "SI_11") (pintype "input"))
      (node (ref "KEY_REG_3") (pin "3") (pinfunction "Q8_3") (pintype "output"))
    )
    (net (code "11") (name "LED1-1") (class "Default")
      (node (ref "LED_REG_1") (pin "15") (pinfunction "QA_15") (pintype "tri_state"))
      (node (ref "R1") (pin "P$2") (pinfunction "2_P$2") (pintype "passive"))
    )
    (net (code "12") (name "LED1-2") (class "Default")
      (node (ref "LED_REG_1") (pin "1") (pinfunction "QB_1") (pintype "tri_state"))
      (node (ref "R2") (pin "P$2") (pinfunction "2_P$2") (pintype "passive"))
    )
    (net (code "13") (name "LED1-3") (class "Default")
      (node (ref "LED_REG_1") (pin "2") (pinfunction "QC_2") (pintype "tri_state"))
      (node (ref "R3") (pin "P$2") (pinfunction "2_P$2") (pintype "passive"))
    )
    (net (code "14") (name "LED1-4") (class "Default")
      (node (ref "LED_REG_1") (pin "3") (pinfunction "QD_3") (pintype "tri_state"))
      (node (ref "R4") (pin "P$2") (pinfunction "2_P$2") (pintype "passive"))
    )
    (net (code "15") (name "LED1-5") (class "Default")
      (node (ref "LED_REG_1") (pin "4") (pinfunction "QE_4") (pintype "tri_state"))
      (node (ref "R5") (pin "P$2") (pinfunction "2_P$2") (pintype "passive"))
    )
    (net (code "16") (name "LED1-6") (class "Default")
      (node (ref "LED_REG_1") (pin "5") (pinfunction "QF_5") (pintype "tri_state"))
      (node (ref "R6") (pin "P$2") (pinfunction "2_P$2") (pintype "passive"))
    )
    (net (code "17") (name "LED1-7") (class "Default")
      (node (ref "LED_REG_1") (pin "6") (pinfunction "QG_6") (pintype "tri_state"))
      (node (ref "R7") (pin "P$2") (pinfunction "2_P$2") (pintype "passive"))
    )
    (net (code "18") (name "LED1-8") (class "Default")
      (node (ref "LED_REG_1") (pin "7") (pinfunction "QH_7") (pintype "tri_state"))
      (node (ref "R8") (pin "P$2") (pinfunction "2_P$2") (pintype "passive"))
    )
    (net (code "19") (name "LED2-1") (class "Default")
      (node (ref "LED_REG_2") (pin "15") (pinfunction "QA_15") (pintype "tri_state"))
      (node (ref "R9") (pin "P$2") (pinfunction "2_P$2") (pintype "passive"))
    )
    (net (code "20") (name "LED2-2") (class "Default")
      (node (ref "LED_REG_2") (pin "1") (pinfunction "QB_1") (pintype "tri_state"))
      (node (ref "R10") (pin "P$2") (pinfunction "2_P$2") (pintype "passive"))
    )
    (net (code "21") (name "LED2-3") (class "Default")
      (node (ref "LED_REG_2") (pin "2") (pinfunction "QC_2") (pintype "tri_state"))
      (node (ref "R11") (pin "P$2") (pinfunction "2_P$2") (pintype "passive"))
    )
    (net (code "22") (name "LED2-4") (class "Default")
      (node (ref "LED_REG_2") (pin "3") (pinfunction "QD_3") (pintype "tri_state"))
      (node (ref "R12") (pin "P$2") (pinfunction "2_P$2") (pintype "passive"))
    )
    (net (code "23") (name "LED2-5") (class "Default")
      (node (ref "LED_REG_2") (pin "4") (pinfunction "QE_4") (pintype "tri_state"))
      (node (ref "R13") (pin "P$2") (pinfunction "2_P$2") (pintype "passive"))
    )
    (net (code "24") (name "LED2-6") (class "Default")
      (node (ref "LED_REG_2") (pin "5") (pinfunction "QF_5") (pintype "tri_state"))
      (node (ref "R14") (pin "P$2") (pinfunction "2_P$2") (pintype "passive"))
    )
    (net (code "25") (name "LED2-7") (class "Default")
      (node (ref "LED_REG_2") (pin "6") (pinfunction "QG_6") (pintype "tri_state"))
      (node (ref "R15") (pin "P$2") (pinfunction "2_P$2") (pintype "passive"))
    )
    (net (code "26") (name "LED2-8") (class "Default")
      (node (ref "LED_REG_2") (pin "7") (pinfunction "QH_7") (pintype "tri_state"))
      (node (ref "R16") (pin "P$2") (pinfunction "2_P$2") (pintype "passive"))
    )
    (net (code "27") (name "LED3-1") (class "Default")
      (node (ref "LED_REG_3") (pin "15") (pinfunction "QA_15") (pintype "tri_state"))
      (node (ref "R17") (pin "P$2") (pinfunction "2_P$2") (pintype "passive"))
    )
    (net (code "28") (name "LED3-2") (class "Default")
      (node (ref "LED_REG_3") (pin "1") (pinfunction "QB_1") (pintype "tri_state"))
      (node (ref "R18") (pin "P$2") (pinfunction "2_P$2") (pintype "passive"))
    )
    (net (code "29") (name "LED3-3") (class "Default")
      (node (ref "LED_REG_3") (pin "2") (pinfunction "QC_2") (pintype "tri_state"))
      (node (ref "R19") (pin "P$2") (pinfunction "2_P$2") (pintype "passive"))
    )
    (net (code "30") (name "LED3-4") (class "Default")
      (node (ref "LED_REG_3") (pin "3") (pinfunction "QD_3") (pintype "tri_state"))
      (node (ref "R20") (pin "P$2") (pinfunction "2_P$2") (pintype "passive"))
    )
    (net (code "31") (name "LED3-5") (class "Default")
      (node (ref "LED_REG_3") (pin "4") (pinfunction "QE_4") (pintype "tri_state"))
      (node (ref "R21") (pin "P$2") (pinfunction "2_P$2") (pintype "passive"))
    )
    (net (code "32") (name "LED3-6") (class "Default")
      (node (ref "LED_REG_3") (pin "5") (pinfunction "QF_5") (pintype "tri_state"))
      (node (ref "R22") (pin "P$2") (pinfunction "2_P$2") (pintype "passive"))
    )
    (net (code "33") (name "LED3-7") (class "Default")
      (node (ref "LED_REG_3") (pin "6") (pinfunction "QG_6") (pintype "tri_state"))
      (node (ref "R23") (pin "P$2") (pinfunction "2_P$2") (pintype "passive"))
    )
    (net (code "34") (name "LED3-8") (class "Default")
      (node (ref "LED_REG_3") (pin "7") (pinfunction "QH_7") (pintype "tri_state"))
      (node (ref "R24") (pin "P$2") (pinfunction "2_P$2") (pintype "passive"))
    )
    (net (code "35") (name "LED_DATA") (class "Default")
      (node (ref "B1") (pin "7") (pinfunction "4_7") (pintype "bidirectional"))
      (node (ref "LED_REG_1") (pin "14") (pinfunction "SER_14") (pintype "input"))
    )
    (net (code "36") (name "LED_LATCH") (class "Default")
      (node (ref "B1") (pin "8") (pinfunction "*5_8") (pintype "bidirectional"))
      (node (ref "LED_REG_1") (pin "12") (pinfunction "RCK_12") (pintype "input"))
      (node (ref "LED_REG_2") (pin "12") (pinfunction "RCK_12") (pintype "input"))
      (node (ref "LED_REG_3") (pin "12") (pinfunction "RCK_12") (pintype "input"))
    )
    (net (code "37") (name "LED_OUTPUT_EN") (class "Default")
      (node (ref "B1") (pin "9") (pinfunction "*6_9") (pintype "bidirectional"))
      (node (ref "LED_REG_1") (pin "13") (pinfunction "G_13") (pintype "input"))
      (node (ref "LED_REG_2") (pin "13") (pinfunction "G_13") (pintype "input"))
      (node (ref "LED_REG_3") (pin "13") (pinfunction "G_13") (pintype "input"))
    )
    (net (code "38") (name "LREG1-2_DATA") (class "Default")
      (node (ref "LED_REG_1") (pin "9") (pinfunction "QH*_9") (pintype "tri_state"))
      (node (ref "LED_REG_2") (pin "14") (pinfunction "SER_14") (pintype "input"))
    )
    (net (code "39") (name "LREG2-3_DATA") (class "Default")
      (node (ref "LED_REG_2") (pin "9") (pinfunction "QH*_9") (pintype "tri_state"))
      (node (ref "LED_REG_3") (pin "14") (pinfunction "SER_14") (pintype "input"))
    )
    (net (code "40") (name "Net-(R1-1)") (class "Default")
      (node (ref "D1") (pin "A") (pinfunction "A_A") (pintype "passive"))
      (node (ref "R1") (pin "P$1") (pinfunction "1_P$1") (pintype "passive"))
      (node (ref "S1") (pin "A") (pinfunction "A_A") (pintype "passive"))
    )
    (net (code "41") (name "Net-(R2-1)") (class "Default")
      (node (ref "D2") (pin "A") (pinfunction "A_A") (pintype "passive"))
      (node (ref "R2") (pin "P$1") (pinfunction "1_P$1") (pintype "passive"))
      (node (ref "S2") (pin "A") (pinfunction "A_A") (pintype "passive"))
    )
    (net (code "42") (name "Net-(R3-1)") (class "Default")
      (node (ref "D3") (pin "A") (pinfunction "A_A") (pintype "passive"))
      (node (ref "R3") (pin "P$1") (pinfunction "1_P$1") (pintype "passive"))
      (node (ref "S3") (pin "A") (pinfunction "A_A") (pintype "passive"))
    )
    (net (code "43") (name "Net-(R4-1)") (class "Default")
      (node (ref "D4") (pin "A") (pinfunction "A_A") (pintype "passive"))
      (node (ref "R4") (pin "P$1") (pinfunction "1_P$1") (pintype "passive"))
      (node (ref "S4") (pin "A") (pinfunction "A_A") (pintype "passive"))
    )
    (net (code "44") (name "Net-(R5-1)") (class "Default")
      (node (ref "D5") (pin "A") (pinfunction "A_A") (pintype "passive"))
      (node (ref "R5") (pin "P$1") (pinfunction "1_P$1") (pintype "passive"))
      (node (ref "S5") (pin "A") (pinfunction "A_A") (pintype "passive"))
    )
    (net (code "45") (name "Net-(R6-1)") (class "Default")
      (node (ref "D6") (pin "A") (pinfunction "A_A") (pintype "passive"))
      (node (ref "R6") (pin "P$1") (pinfunction "1_P$1") (pintype "passive"))
      (node (ref "S6") (pin "A") (pinfunction "A_A") (pintype "passive"))
    )
    (net (code "46") (name "Net-(R7-1)") (class "Default")
      (node (ref "D7") (pin "A") (pinfunction "A_A") (pintype "passive"))
      (node (ref "R7") (pin "P$1") (pinfunction "1_P$1") (pintype "passive"))
      (node (ref "S7") (pin "A") (pinfunction "A_A") (pintype "passive"))
    )
    (net (code "47") (name "Net-(R8-1)") (class "Default")
      (node (ref "D8") (pin "A") (pinfunction "A_A") (pintype "passive"))
      (node (ref "R8") (pin "P$1") (pinfunction "1_P$1") (pintype "passive"))
      (node (ref "S8") (pin "A") (pinfunction "A_A") (pintype "passive"))
    )
    (net (code "48") (name "Net-(R9-1)") (class "Default")
      (node (ref "D9") (pin "A") (pinfunction "A_A") (pintype "passive"))
      (node (ref "R9") (pin "P$1") (pinfunction "1_P$1") (pintype "passive"))
      (node (ref "S9") (pin "A") (pinfunction "A_A") (pintype "passive"))
    )
    (net (code "49") (name "Net-(R10-1)") (class "Default")
      (node (ref "D10") (pin "A") (pinfunction "A_A") (pintype "passive"))
      (node (ref "R10") (pin "P$1") (pinfunction "1_P$1") (pintype "passive"))
      (node (ref "S10") (pin "A") (pinfunction "A_A") (pintype "passive"))
    )
    (net (code "50") (name "Net-(R11-1)") (class "Default")
      (node (ref "D11") (pin "A") (pinfunction "A_A") (pintype "passive"))
      (node (ref "R11") (pin "P$1") (pinfunction "1_P$1") (pintype "passive"))
      (node (ref "S11") (pin "A") (pinfunction "A_A") (pintype "passive"))
    )
    (net (code "51") (name "Net-(R12-1)") (class "Default")
      (node (ref "D12") (pin "A") (pinfunction "A_A") (pintype "passive"))
      (node (ref "R12") (pin "P$1") (pinfunction "1_P$1") (pintype "passive"))
      (node (ref "S12") (pin "A") (pinfunction "A_A") (pintype "passive"))
    )
    (net (code "52") (name "Net-(R13-1)") (class "Default")
      (node (ref "D13") (pin "A") (pinfunction "A_A") (pintype "passive"))
      (node (ref "R13") (pin "P$1") (pinfunction "1_P$1") (pintype "passive"))
      (node (ref "S13") (pin "A") (pinfunction "A_A") (pintype "passive"))
    )
    (net (code "53") (name "Net-(R14-1)") (class "Default")
      (node (ref "D14") (pin "A") (pinfunction "A_A") (pintype "passive"))
      (node (ref "R14") (pin "P$1") (pinfunction "1_P$1") (pintype "passive"))
      (node (ref "S14") (pin "A") (pinfunction "A_A") (pintype "passive"))
    )
    (net (code "54") (name "Net-(R15-1)") (class "Default")
      (node (ref "D15") (pin "A") (pinfunction "A_A") (pintype "passive"))
      (node (ref "R15") (pin "P$1") (pinfunction "1_P$1") (pintype "passive"))
      (node (ref "S15") (pin "A") (pinfunction "A_A") (pintype "passive"))
    )
    (net (code "55") (name "Net-(R16-1)") (class "Default")
      (node (ref "D16") (pin "A") (pinfunction "A_A") (pintype "passive"))
      (node (ref "R16") (pin "P$1") (pinfunction "1_P$1") (pintype "passive"))
      (node (ref "S16") (pin "A") (pinfunction "A_A") (pintype "passive"))
    )
    (net (code "56") (name "Net-(R17-1)") (class "Default")
      (node (ref "D17") (pin "A") (pinfunction "A_A") (pintype "passive"))
      (node (ref "R17") (pin "P$1") (pinfunction "1_P$1") (pintype "passive"))
      (node (ref "S17") (pin "A") (pinfunction "A_A") (pintype "passive"))
    )
    (net (code "57") (name "Net-(R18-1)") (class "Default")
      (node (ref "D18") (pin "A") (pinfunction "A_A") (pintype "passive"))
      (node (ref "R18") (pin "P$1") (pinfunction "1_P$1") (pintype "passive"))
      (node (ref "S18") (pin "A") (pinfunction "A_A") (pintype "passive"))
    )
    (net (code "58") (name "Net-(R19-1)") (class "Default")
      (node (ref "D19") (pin "A") (pinfunction "A_A") (pintype "passive"))
      (node (ref "R19") (pin "P$1") (pinfunction "1_P$1") (pintype "passive"))
      (node (ref "S19") (pin "A") (pinfunction "A_A") (pintype "passive"))
    )
    (net (code "59") (name "Net-(R20-1)") (class "Default")
      (node (ref "D20") (pin "A") (pinfunction "A_A") (pintype "passive"))
      (node (ref "R20") (pin "P$1") (pinfunction "1_P$1") (pintype "passive"))
      (node (ref "S20") (pin "A") (pinfunction "A_A") (pintype "passive"))
    )
    (net (code "60") (name "Net-(R21-1)") (class "Default")
      (node (ref "D21") (pin "A") (pinfunction "A_A") (pintype "passive"))
      (node (ref "R21") (pin "P$1") (pinfunction "1_P$1") (pintype "passive"))
      (node (ref "S21") (pin "A") (pinfunction "A_A") (pintype "passive"))
    )
    (net (code "61") (name "Net-(R22-1)") (class "Default")
      (node (ref "D22") (pin "A") (pinfunction "A_A") (pintype "passive"))
      (node (ref "R22") (pin "P$1") (pinfunction "1_P$1") (pintype "passive"))
      (node (ref "S22") (pin "A") (pinfunction "A_A") (pintype "passive"))
    )
    (net (code "62") (name "Net-(R23-1)") (class "Default")
      (node (ref "D23") (pin "A") (pinfunction "A_A") (pintype "passive"))
      (node (ref "R23") (pin "P$1") (pinfunction "1_P$1") (pintype "passive"))
      (node (ref "S23") (pin "A") (pinfunction "A_A") (pintype "passive"))
    )
    (net (code "63") (name "Net-(R24-1)") (class "Default")
      (node (ref "D24") (pin "A") (pinfunction "A_A") (pintype "passive"))
      (node (ref "R24") (pin "P$1") (pinfunction "1_P$1") (pintype "passive"))
      (node (ref "S24") (pin "A") (pinfunction "A_A") (pintype "passive"))
    )
    (net (code "64") (name "Net-(R54-2)") (class "Default")
      (node (ref "R54") (pin "P$2") (pinfunction "2_P$2") (pintype "passive"))
      (node (ref "S28") (pin "+G") (pinfunction "+G_+G") (pintype "passive"))
    )
    (net (code "65") (name "Net-(R55-2)") (class "Default")
      (node (ref "R55") (pin "P$2") (pinfunction "2_P$2") (pintype "passive"))
      (node (ref "S28") (pin "+R") (pinfunction "+R_+R") (pintype "passive"))
    )
    (net (code "66") (name "OCTAVE_DOWN") (class "Default")
      (node (ref "B1") (pin "14") (pinfunction "11(MOSI)_14") (pintype "bidirectional"))
      (node (ref "R50") (pin "P$2") (pinfunction "2_P$2") (pintype "passive"))
      (node (ref "S27") (pin "S2") (pinfunction "2_S2") (pintype "passive"))
    )
    (net (code "67") (name "OCTAVE_UP") (class "Default")
      (node (ref "B1") (pin "15") (pinfunction "12(MISO)_15") (pintype "bidirectional"))
      (node (ref "R49") (pin "P$2") (pinfunction "2_P$2") (pintype "passive"))
      (node (ref "S26") (pin "S2") (pinfunction "2_S2") (pintype "passive"))
    )
    (net (code "68") (name "RAW") (class "Default")
      (node (ref "B1") (pin "24") (pinfunction "RAW_24") (pintype "power_in"))
    )
    (net (code "69") (name "REGISTER_CLOCK") (class "Default")
      (node (ref "B1") (pin "12") (pinfunction "*9_12") (pintype "bidirectional"))
      (node (ref "KEY_REG_1") (pin "10") (pinfunction "CLK_10") (pintype "input"))
      (node (ref "KEY_REG_2") (pin "10") (pinfunction "CLK_10") (pintype "input"))
      (node (ref "KEY_REG_3") (pin "10") (pinfunction "CLK_10") (pintype "input"))
      (node (ref "LED_REG_1") (pin "11") (pinfunction "SCK_11") (pintype "input"))
      (node (ref "LED_REG_2") (pin "11") (pinfunction "SCK_11") (pintype "input"))
      (node (ref "LED_REG_3") (pin "11") (pinfunction "SCK_11") (pintype "input"))
    )
    (net (code "70") (name "RESET") (class "Default")
      (node (ref "B1") (pin "22") (pinfunction "RESET_22") (pintype "bidirectional"))
      (node (ref "S25") (pin "1") (pinfunction "1_1") (pintype "passive"))
    )
    (net (code "71") (name "SCL") (class "Default")
      (node (ref "B1") (pin "6") (pinfunction "*3_6") (pintype "bidirectional"))
      (node (ref "J1") (pin "3") (pinfunction "3_3") (pintype "passive"))
      (node (ref "R51") (pin "P$1") (pinfunction "1_P$1") (pintype "passive"))
    )
    (net (code "72") (name "SDA") (class "Default")
      (node (ref "B1") (pin "5") (pinfunction "2_5") (pintype "bidirectional"))
      (node (ref "J1") (pin "4") (pinfunction "4_4") (pintype "passive"))
      (node (ref "R52") (pin "P$1") (pinfunction "1_P$1") (pintype "passive"))
    )
    (net (code "73") (name "SWITCH1-1") (class "Default")
      (node (ref "KEY_REG_1") (pin "7") (pinfunction "P1_7") (pintype "input"))
      (node (ref "R25") (pin "P$1") (pinfunction "1_P$1") (pintype "passive"))
      (node (ref "S1") (pin "S2") (pinfunction "2_S2") (pintype "passive"))
    )
    (net (code "74") (name "SWITCH1-2") (class "Default")
      (node (ref "KEY_REG_1") (pin "6") (pinfunction "P2_6") (pintype "input"))
      (node (ref "R26") (pin "P$1") (pinfunction "1_P$1") (pintype "passive"))
      (node (ref "S2") (pin "S2") (pinfunction "2_S2") (pintype "passive"))
    )
    (net (code "75") (name "SWITCH1-3") (class "Default")
      (node (ref "KEY_REG_1") (pin "5") (pinfunction "P3_5") (pintype "input"))
      (node (ref "R27") (pin "P$1") (pinfunction "1_P$1") (pintype "passive"))
      (node (ref "S3") (pin "S2") (pinfunction "2_S2") (pintype "passive"))
    )
    (net (code "76") (name "SWITCH1-4") (class "Default")
      (node (ref "KEY_REG_1") (pin "4") (pinfunction "P4_4") (pintype "input"))
      (node (ref "R28") (pin "P$1") (pinfunction "1_P$1") (pintype "passive"))
      (node (ref "S4") (pin "S2") (pinfunction "2_S2") (pintype "passive"))
    )
    (net (code "77") (name "SWITCH1-5") (class "Default")
      (node (ref "KEY_REG_1") (pin "13") (pinfunction "P5_13") (pintype "input"))
      (node (ref "R29") (pin "P$1") (pinfunction "1_P$1") (pintype "passive"))
      (node (ref "S5") (pin "S2") (pinfunction "2_S2") (pintype "passive"))
    )
    (net (code "78") (name "SWITCH1-6") (class "Default")
      (node (ref "KEY_REG_1") (pin "14") (pinfunction "P6_14") (pintype "input"))
      (node (ref "R30") (pin "P$1") (pinfunction "1_P$1") (pintype "passive"))
      (node (ref "S6") (pin "S2") (pinfunction "2_S2") (pintype "passive"))
    )
    (net (code "79") (name "SWITCH1-7") (class "Default")
      (node (ref "KEY_REG_1") (pin "15") (pinfunction "P7_15") (pintype "input"))
      (node (ref "R31") (pin "P$1") (pinfunction "1_P$1") (pintype "passive"))
      (node (ref "S7") (pin "S2") (pinfunction "2_S2") (pintype "passive"))
    )
    (net (code "80") (name "SWITCH1-8") (class "Default")
      (node (ref "KEY_REG_1") (pin "1") (pinfunction "P8_1") (pintype "input"))
      (node (ref "R32") (pin "P$1") (pinfunction "1_P$1") (pintype "passive"))
      (node (ref "S8") (pin "S2") (pinfunction "2_S2") (pintype "passive"))
    )
    (net (code "81") (name "SWITCH2-1") (class "Default")
      (node (ref "KEY_REG_2") (pin "7") (pinfunction "P1_7") (pintype "input"))
      (node (ref "R33") (pin "P$1") (pinfunction "1_P$1") (pintype "passive"))
      (node (ref "S9") (pin "S2") (pinfunction "2_S2") (pintype "passive"))
    )
    (net (code "82") (name "SWITCH2-2") (class "Default")
      (node (ref "KEY_REG_2") (pin "6") (pinfunction "P2_6") (pintype "input"))
      (node (ref "R34") (pin "P$1") (pinfunction "1_P$1") (pintype "passive"))
      (node (ref "S10") (pin "S2") (pinfunction "2_S2") (pintype "passive"))
    )
    (net (code "83") (name "SWITCH2-3") (class "Default")
      (node (ref "KEY_REG_2") (pin "5") (pinfunction "P3_5") (pintype "input"))
      (node (ref "R35") (pin "P$1") (pinfunction "1_P$1") (pintype "passive"))
      (node (ref "S11") (pin "S2") (pinfunction "2_S2") (pintype "passive"))
    )
    (net (code "84") (name "SWITCH2-4") (class "Default")
      (node (ref "KEY_REG_2") (pin "4") (pinfunction "P4_4") (pintype "input"))
      (node (ref "R36") (pin "P$1") (pinfunction "1_P$1") (pintype "passive"))
      (node (ref "S12") (pin "S2") (pinfunction "2_S2") (pintype "passive"))
    )
    (net (code "85") (name "SWITCH2-5") (class "Default")
      (node (ref "KEY_REG_2") (pin "13") (pinfunction "P5_13") (pintype "input"))
      (node (ref "R37") (pin "P$1") (pinfunction "1_P$1") (pintype "passive"))
      (node (ref "S13") (pin "S2") (pinfunction "2_S2") (pintype "passive"))
    )
    (net (code "86") (name "SWITCH2-6") (class "Default")
      (node (ref "KEY_REG_2") (pin "14") (pinfunction "P6_14") (pintype "input"))
      (node (ref "R38") (pin "P$1") (pinfunction "1_P$1") (pintype "passive"))
      (node (ref "S14") (pin "S2") (pinfunction "2_S2") (pintype "passive"))
    )
    (net (code "87") (name "SWITCH2-7") (class "Default")
      (node (ref "KEY_REG_2") (pin "15") (pinfunction "P7_15") (pintype "input"))
      (node (ref "R39") (pin "P$1") (pinfunction "1_P$1") (pintype "passive"))
      (node (ref "S15") (pin "S2") (pinfunction "2_S2") (pintype "passive"))
    )
    (net (code "88") (name "SWITCH2-8") (class "Default")
      (node (ref "KEY_REG_2") (pin "1") (pinfunction "P8_1") (pintype "input"))
      (node (ref "R40") (pin "P$1") (pinfunction "1_P$1") (pintype "passive"))
      (node (ref "S16") (pin "S2") (pinfunction "2_S2") (pintype "passive"))
    )
    (net (code "89") (name "SWITCH3-1") (class "Default")
      (node (ref "KEY_REG_3") (pin "7") (pinfunction "P1_7") (pintype "input"))
      (node (ref "R41") (pin "P$1") (pinfunction "1_P$1") (pintype "passive"))
      (node (ref "S17") (pin "S2") (pinfunction "2_S2") (pintype "passive"))
    )
    (net (code "90") (name "SWITCH3-2") (class "Default")
      (node (ref "KEY_REG_3") (pin "6") (pinfunction "P2_6") (pintype "input"))
      (node (ref "R42") (pin "P$1") (pinfunction "1_P$1") (pintype "passive"))
      (node (ref "S18") (pin "S2") (pinfunction "2_S2") (pintype "passive"))
    )
    (net (code "91") (name "SWITCH3-3") (class "Default")
      (node (ref "KEY_REG_3") (pin "5") (pinfunction "P3_5") (pintype "input"))
      (node (ref "R43") (pin "P$1") (pinfunction "1_P$1") (pintype "passive"))
      (node (ref "S19") (pin "S2") (pinfunction "2_S2") (pintype "passive"))
    )
    (net (code "92") (name "SWITCH3-4") (class "Default")
      (node (ref "KEY_REG_3") (pin "4") (pinfunction "P4_4") (pintype "input"))
      (node (ref "R44") (pin "P$1") (pinfunction "1_P$1") (pintype "passive"))
      (node (ref "S20") (pin "S2") (pinfunction "2_S2") (pintype "passive"))
    )
    (net (code "93") (name "SWITCH3-5") (class "Default")
      (node (ref "KEY_REG_3") (pin "13") (pinfunction "P5_13") (pintype "input"))
      (node (ref "R45") (pin "P$1") (pinfunction "1_P$1") (pintype "passive"))
      (node (ref "S21") (pin "S2") (pinfunction "2_S2") (pintype "passive"))
    )
    (net (code "94") (name "SWITCH3-6") (class "Default")
      (node (ref "KEY_REG_3") (pin "14") (pinfunction "P6_14") (pintype "input"))
      (node (ref "R46") (pin "P$1") (pinfunction "1_P$1") (pintype "passive"))
      (node (ref "S22") (pin "S2") (pinfunction "2_S2") (pintype "passive"))
    )
    (net (code "95") (name "SWITCH3-7") (class "Default")
      (node (ref "KEY_REG_3") (pin "15") (pinfunction "P7_15") (pintype "input"))
      (node (ref "R47") (pin "P$1") (pinfunction "1_P$1") (pintype "passive"))
      (node (ref "S23") (pin "S2") (pinfunction "2_S2") (pintype "passive"))
    )
    (net (code "96") (name "SWITCH3-8") (class "Default")
      (node (ref "KEY_REG_3") (pin "1") (pinfunction "P8_1") (pintype "input"))
      (node (ref "R48") (pin "P$1") (pinfunction "1_P$1") (pintype "passive"))
      (node (ref "S24") (pin "S2") (pinfunction "2_S2") (pintype "passive"))
    )
    (net (code "97") (name "VCC") (class "Default")
      (node (ref "B1") (pin "21") (pinfunction "VCC_21") (pintype "power_in"))
      (node (ref "C1") (pin "1") (pinfunction "+_1") (pintype "passive"))
      (node (ref "C2") (pin "1") (pinfunction "+_1") (pintype "passive"))
      (node (ref "C3") (pin "1") (pinfunction "+_1") (pintype "passive"))
      (node (ref "J1") (pin "1") (pinfunction "1_1") (pintype "passive"))
      (node (ref "KEY_REG_1") (pin "16") (pinfunction "VDD_16") (pintype "power_in"))
      (node (ref "KEY_REG_2") (pin "16") (pinfunction "VDD_16") (pintype "power_in"))
      (node (ref "KEY_REG_3") (pin "16") (pinfunction "VDD_16") (pintype "power_in"))
      (node (ref "LED_REG_1") (pin "10") (pinfunction "SCL_10") (pintype "input"))
      (node (ref "LED_REG_1") (pin "16") (pinfunction "VCC_16") (pintype "power_in"))
      (node (ref "LED_REG_2") (pin "10") (pinfunction "SCL_10") (pintype "input"))
      (node (ref "LED_REG_2") (pin "16") (pinfunction "VCC_16") (pintype "power_in"))
      (node (ref "LED_REG_3") (pin "10") (pinfunction "SCL_10") (pintype "input"))
      (node (ref "LED_REG_3") (pin "16") (pinfunction "VCC_16") (pintype "power_in"))
      (node (ref "R51") (pin "P$2") (pinfunction "2_P$2") (pintype "passive"))
      (node (ref "R52") (pin "P$2") (pinfunction "2_P$2") (pintype "passive"))
      (node (ref "R53") (pin "P$2") (pinfunction "2_P$2") (pintype "passive"))
      (node (ref "S1") (pin "S1") (pinfunction "1_S1") (pintype "passive"))
      (node (ref "S10") (pin "S1") (pinfunction "1_S1") (pintype "passive"))
      (node (ref "S11") (pin "S1") (pinfunction "1_S1") (pintype "passive"))
      (node (ref "S12") (pin "S1") (pinfunction "1_S1") (pintype "passive"))
      (node (ref "S13") (pin "S1") (pinfunction "1_S1") (pintype "passive"))
      (node (ref "S14") (pin "S1") (pinfunction "1_S1") (pintype "passive"))
      (node (ref "S15") (pin "S1") (pinfunction "1_S1") (pintype "passive"))
      (node (ref "S16") (pin "S1") (pinfunction "1_S1") (pintype "passive"))
      (node (ref "S17") (pin "S1") (pinfunction "1_S1") (pintype "passive"))
      (node (ref "S18") (pin "S1") (pinfunction "1_S1") (pintype "passive"))
      (node (ref "S19") (pin "S1") (pinfunction "1_S1") (pintype "passive"))
      (node (ref "S2") (pin "S1") (pinfunction "1_S1") (pintype "passive"))
      (node (ref "S20") (pin "S1") (pinfunction "1_S1") (pintype "passive"))
      (node (ref "S21") (pin "S1") (pinfunction "1_S1") (pintype "passive"))
      (node (ref "S22") (pin "S1") (pinfunction "1_S1") (pintype "passive"))
      (node (ref "S23") (pin "S1") (pinfunction "1_S1") (pintype "passive"))
      (node (ref "S24") (pin "S1") (pinfunction "1_S1") (pintype "passive"))
      (node (ref "S26") (pin "S1") (pinfunction "1_S1") (pintype "passive"))
      (node (ref "S27") (pin "S1") (pinfunction "1_S1") (pintype "passive"))
      (node (ref "S3") (pin "S1") (pinfunction "1_S1") (pintype "passive"))
      (node (ref "S4") (pin "S1") (pinfunction "1_S1") (pintype "passive"))
      (node (ref "S5") (pin "S1") (pinfunction "1_S1") (pintype "passive"))
      (node (ref "S6") (pin "S1") (pinfunction "1_S1") (pintype "passive"))
      (node (ref "S7") (pin "S1") (pinfunction "1_S1") (pintype "passive"))
      (node (ref "S8") (pin "S1") (pinfunction "1_S1") (pintype "passive"))
      (node (ref "S9") (pin "S1") (pinfunction "1_S1") (pintype "passive"))
      (node (ref "VR1") (pin "P$3") (pinfunction "A_P$3") (pintype "passive"))
    )
    (net (code "98") (name "VELPOT") (class "Default")
      (node (ref "B1") (pin "13") (pinfunction "*10_13") (pintype "bidirectional"))
      (node (ref "VR1") (pin "P$2") (pinfunction "S_P$2") (pintype "passive"))
    )
    (net (code "99") (name "unconnected-(B1-RXI-Pad2)") (class "Default")
      (node (ref "B1") (pin "2") (pinfunction "RXI_2") (pintype "bidirectional"))
    )
    (net (code "100") (name "unconnected-(B1-TXO-Pad1)") (class "Default")
      (node (ref "B1") (pin "1") (pinfunction "TXO_1") (pintype "bidirectional"))
    )
    (net (code "101") (name "unconnected-(KEY_REG_1A-Q6-Pad2)") (class "Default")
      (node (ref "KEY_REG_1") (pin "2") (pinfunction "Q6_2") (pintype "output"))
    )
    (net (code "102") (name "unconnected-(KEY_REG_1A-Q7-Pad12)") (class "Default")
      (node (ref "KEY_REG_1") (pin "12") (pinfunction "Q7_12") (pintype "output"))
    )
    (net (code "103") (name "unconnected-(KEY_REG_2A-Q6-Pad2)") (class "Default")
      (node (ref "KEY_REG_2") (pin "2") (pinfunction "Q6_2") (pintype "output"))
    )
    (net (code "104") (name "unconnected-(KEY_REG_2A-Q7-Pad12)") (class "Default")
      (node (ref "KEY_REG_2") (pin "12") (pinfunction "Q7_12") (pintype "output"))
    )
    (net (code "105") (name "unconnected-(KEY_REG_3A-Q6-Pad2)") (class "Default")
      (node (ref "KEY_REG_3") (pin "2") (pinfunction "Q6_2") (pintype "output"))
    )
    (net (code "106") (name "unconnected-(KEY_REG_3A-Q7-Pad12)") (class "Default")
      (node (ref "KEY_REG_3") (pin "12") (pinfunction "Q7_12") (pintype "output"))
    )
    (net (code "107") (name "unconnected-(KEY_REG_3A-SI-Pad11)") (class "Default")
      (node (ref "KEY_REG_3") (pin "11") (pinfunction "SI_11") (pintype "input"))
    )
    (net (code "108") (name "unconnected-(LED_REG_3-QH*-Pad9)") (class "Default")
      (node (ref "LED_REG_3") (pin "9") (pinfunction "QH*_9") (pintype "tri_state"))
    )
    (net (code "109") (name "unconnected-(S26-C-PadK)") (class "Default")
      (node (ref "S26") (pin "K") (pinfunction "C_K") (pintype "passive"))
    )
    (net (code "110") (name "unconnected-(S26-PadA)") (class "Default")
      (node (ref "S26") (pin "A") (pinfunction "A_A") (pintype "passive"))
    )
    (net (code "111") (name "unconnected-(S27-C-PadK)") (class "Default")
      (node (ref "S27") (pin "K") (pinfunction "C_K") (pintype "passive"))
    )
    (net (code "112") (name "unconnected-(S27-PadA)") (class "Default")
      (node (ref "S27") (pin "A") (pinfunction "A_A") (pintype "passive"))
    )
  )
)
